# LTEModule.net
KiCad netlist of a schematic drawn in Altium Designer
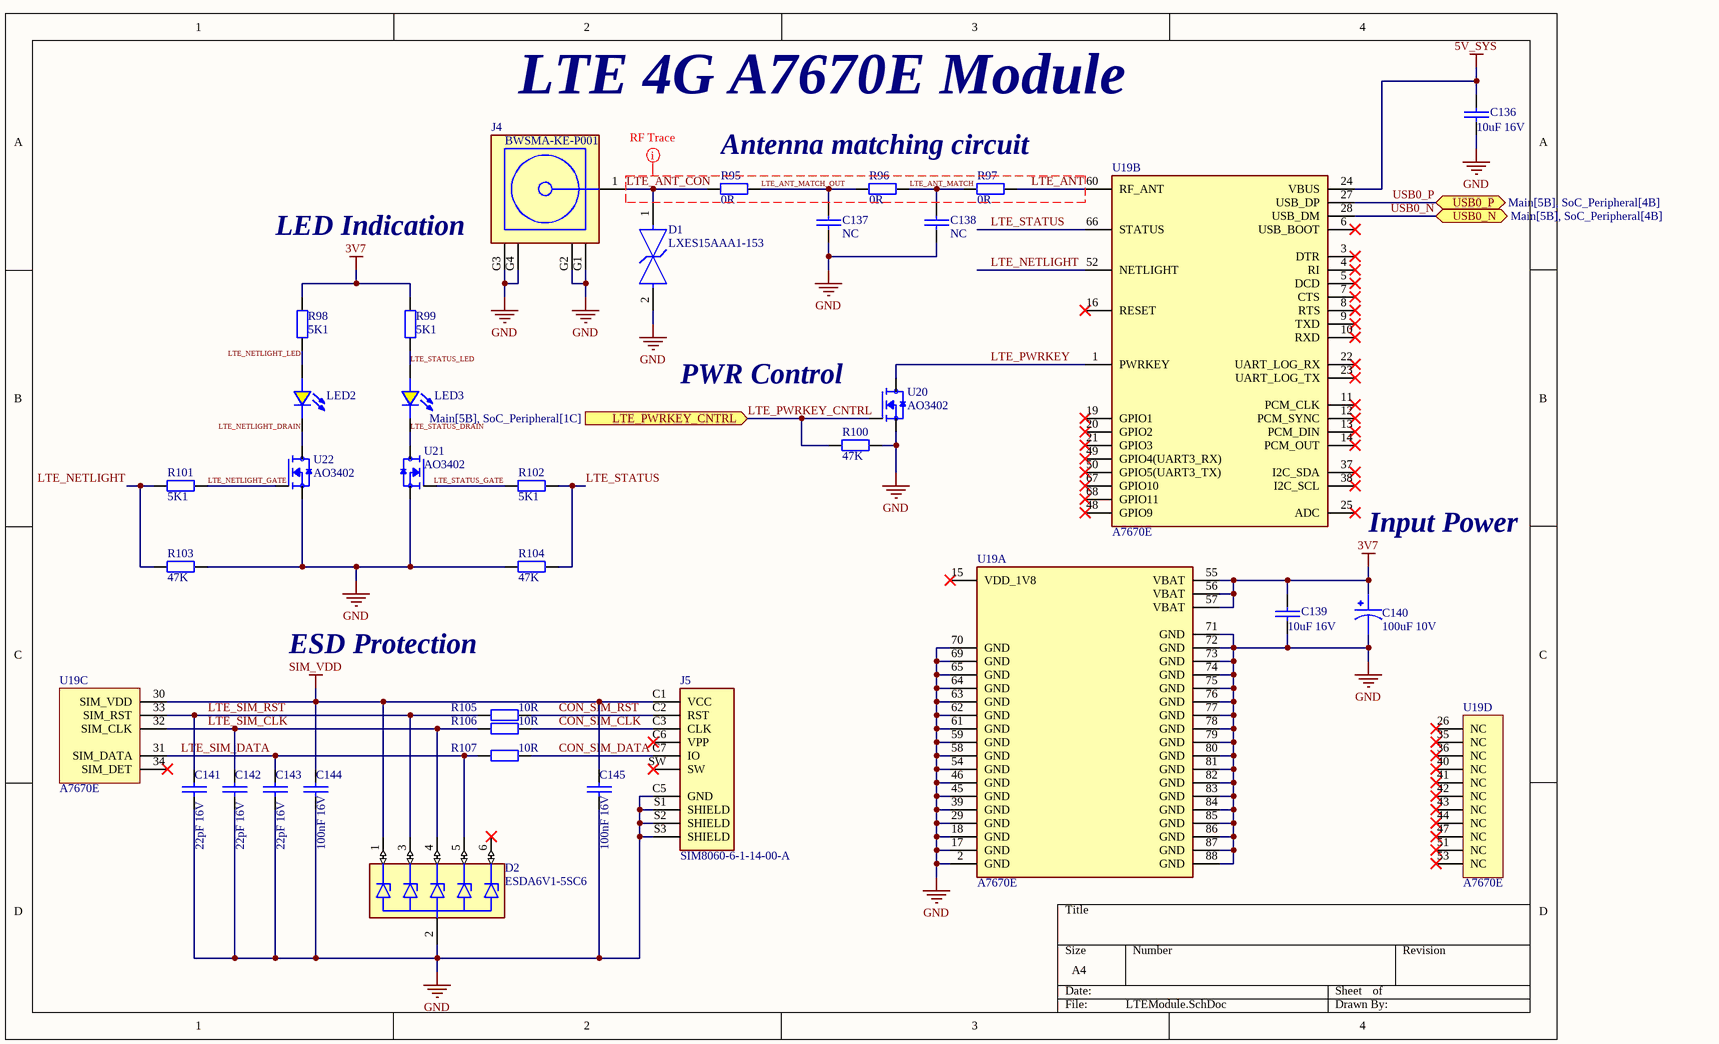
[diagram p0: LTEModule.SchDoc]

(export (version "E")
  (design (tool "Eeschema 10.0.6"))
  (components
    (comp (ref "C136")
      (value "10uF 16V")
      (footprint "C_0603")
      (description "Capacitor 0603 SMD")
      (libsource (lib "tor1kkLib") (part "C_0603"))
    )
    (comp (ref "C137")
      (value "NC")
      (footprint "C_0402")
      (description "Capacitor 0402 SMD")
      (libsource (lib "tor1kkLib") (part "C_0402"))
    )
    (comp (ref "C138")
      (value "NC")
      (footprint "C_0402")
      (description "Capacitor 0402 SMD")
      (libsource (lib "tor1kkLib") (part "C_0402"))
    )
    (comp (ref "C139")
      (value "10uF 16V")
      (footprint "C_0603")
      (description "Capacitor 0603 SMD")
      (libsource (lib "tor1kkLib") (part "C_0603"))
    )
    (comp (ref "C140")
      (value "100uF 10V")
      (footprint "C_CASE-B")
      (description "Tantalum capacitor CASE-B-3528-21")
      (libsource (lib "tor1kkLib") (part "C_CASE-B-3528-21"))
    )
    (comp (ref "C141")
      (value "22pF 16V")
      (footprint "C_0402")
      (description "Capacitor 0402 SMD")
      (libsource (lib "tor1kkLib") (part "C_0402"))
    )
    (comp (ref "C142")
      (value "22pF 16V")
      (footprint "C_0402")
      (description "Capacitor 0402 SMD")
      (libsource (lib "tor1kkLib") (part "C_0402"))
    )
    (comp (ref "C143")
      (value "22pF 16V")
      (footprint "C_0402")
      (description "Capacitor 0402 SMD")
      (libsource (lib "tor1kkLib") (part "C_0402"))
    )
    (comp (ref "C144")
      (value "100nF 16V")
      (footprint "C_0402")
      (description "Capacitor 0402 SMD")
      (libsource (lib "tor1kkLib") (part "C_0402"))
    )
    (comp (ref "C145")
      (value "100nF 16V")
      (footprint "C_0402")
      (description "Capacitor 0402 SMD")
      (libsource (lib "tor1kkLib") (part "C_0402"))
    )
    (comp (ref "D1")
      (value "LXES15AAA1-153")
      (footprint "FP-LXES15-MFG")
      (description "TVS DIODE 4V 1005")
      (libsource (lib "Altium Content Vault") (part "876f4347bf90aa6f500f43e3cd03972"))
    )
    (comp (ref "D2")
      (value "ESDA6V1-5SC6")
      (footprint "SOT-23-6")
      (description "11.4V Clamp 7A (8/20µs) Ipp Tvs Diode Surface Mount SOT-23-6")
      (fields (field (name "MANUFACTURER") "STMicroelectronics"))
      (libsource (lib "tor1kkLib") (part "ESDA6V1-5SC6"))
    )
    (comp (ref "J4")
      (value "BWSMA-KE-P001")
      (footprint "BATWIRELESS_BWSMA-KE-P001")
      (description "1 Inner Hole SMA Board-End Staggered pins 50Ω 5.2mm SMD Coaxial Connectors (RF) ROHS")
      (fields (field (name "MANUFACTURER") "BAT WIRELESS"))
      (libsource (lib "tor1kkLib") (part "BWSMA-KE-P001"))
    )
    (comp (ref "J5")
      (value "SIM8060-6-1-14-00-A")
      (footprint "SIM8060-6-1-14-00-A")
      (description "6 Position Card Connector NANO SIM Surface Mount, Right Angle Gold")
      (fields (field (name "MANUFACTURER") "Global Connector Technology"))
      (libsource (lib "tor1kkLib") (part "SIM8060-6-1-14-00-A"))
    )
    (comp (ref "LED2")
      (value "LED_0603_YELLOW")
      (footprint "LED_0603")
      (libsource (lib "tor1kkLib") (part "LED_0603_YELLOW"))
    )
    (comp (ref "LED3")
      (value "LED_0603_YELLOW")
      (footprint "LED_0603")
      (libsource (lib "tor1kkLib") (part "LED_0603_YELLOW"))
    )
    (comp (ref "R95")
      (value "0R")
      (footprint "R_0402")
      (description "Resistor 0402 SMD")
      (libsource (lib "tor1kkLib") (part "R_0402"))
    )
    (comp (ref "R96")
      (value "0R")
      (footprint "R_0402")
      (description "Resistor 0402 SMD")
      (libsource (lib "tor1kkLib") (part "R_0402"))
    )
    (comp (ref "R97")
      (value "0R")
      (footprint "R_0402")
      (description "Resistor 0402 SMD")
      (libsource (lib "tor1kkLib") (part "R_0402"))
    )
    (comp (ref "R98")
      (value "5K1")
      (footprint "R_0603")
      (description "Resistor 0603 SMD")
      (libsource (lib "tor1kkLib") (part "R_0603"))
    )
    (comp (ref "R99")
      (value "5K1")
      (footprint "R_0603")
      (description "Resistor 0603 SMD")
      (libsource (lib "tor1kkLib") (part "R_0603"))
    )
    (comp (ref "R100")
      (value "47K")
      (footprint "R_0603")
      (description "Resistor 0603 SMD")
      (libsource (lib "") (part "R_0603_1"))
    )
    (comp (ref "R101")
      (value "5K1")
      (footprint "R_0603")
      (description "Resistor 0603 SMD")
      (libsource (lib "") (part "R_0603_1"))
    )
    (comp (ref "R102")
      (value "5K1")
      (footprint "R_0603")
      (description "Resistor 0603 SMD")
      (libsource (lib "") (part "R_0603_1"))
    )
    (comp (ref "R103")
      (value "47K")
      (footprint "R_0603")
      (description "Resistor 0603 SMD")
      (libsource (lib "") (part "R_0603_1"))
    )
    (comp (ref "R104")
      (value "47K")
      (footprint "R_0603")
      (description "Resistor 0603 SMD")
      (libsource (lib "") (part "R_0603_1"))
    )
    (comp (ref "R105")
      (value "10R")
      (footprint "R_0402")
      (description "Resistor 0402 SMD")
      (libsource (lib "") (part "R_0402_1"))
    )
    (comp (ref "R106")
      (value "10R")
      (footprint "R_0402")
      (description "Resistor 0402 SMD")
      (libsource (lib "") (part "R_0402_1"))
    )
    (comp (ref "R107")
      (value "10R")
      (footprint "R_0402")
      (description "Resistor 0402 SMD")
      (libsource (lib "") (part "R_0402_1"))
    )
    (comp (ref "U19")
      (value "A7670E")
      (footprint "A7670")
      (description "LTE Cat 1 module")
      (fields
        (field (name "MANUFACTURER") "SIMCom Wireless Solutions")
        (field (name "MANUFACTURER PART NUMBER") "A7670E-LASE")
      )
      (libsource (lib "tor1kkLib") (part "A7670E"))
    )
    (comp (ref "U20")
      (value "AO3402")
      (footprint "SOT-23-3")
      (description "N-Channel 30 V 4A (Ta) 1.4W (Ta) Surface Mount SOT-23-3")
      (fields (field (name "MANUFACTURER") "Alpha & Omega Semicon"))
      (libsource (lib "tor1kkLib") (part "AO3402"))
    )
    (comp (ref "U21")
      (value "AO3402")
      (footprint "SOT-23-3")
      (description "N-Channel 30 V 4A (Ta) 1.4W (Ta) Surface Mount SOT-23-3")
      (fields (field (name "MANUFACTURER") "Alpha & Omega Semicon"))
      (libsource (lib "tor1kkLib") (part "AO3402"))
    )
    (comp (ref "U22")
      (value "AO3402")
      (footprint "SOT-23-3")
      (description "N-Channel 30 V 4A (Ta) 1.4W (Ta) Surface Mount SOT-23-3")
      (fields (field (name "MANUFACTURER") "Alpha & Omega Semicon"))
      (libsource (lib "tor1kkLib") (part "AO3402"))
    )
  )
  (nets
    (net (code "2") (name "/CON_SIM_CLK") (class "Default")
      (node (ref "J5") (pin "C3") (pinfunction "CLK_C3") (pintype "passive"))
      (node (ref "R106") (pin "1") (pintype "passive"))
    )
    (net (code "3") (name "/CON_SIM_DATA") (class "Default")
      (node (ref "J5") (pin "C7") (pinfunction "IO_C7") (pintype "passive"))
      (node (ref "R107") (pin "1") (pintype "passive"))
    )
    (net (code "4") (name "/CON_SIM_RST") (class "Default")
      (node (ref "J5") (pin "C2") (pinfunction "RST_C2") (pintype "passive"))
      (node (ref "R105") (pin "1") (pintype "passive"))
    )
    (net (code "5") (name "/LTE_ANT") (class "Default")
      (node (ref "R97") (pin "2") (pintype "passive"))
      (node (ref "U19") (pin "60") (pinfunction "RF_ANT_60") (pintype "passive"))
    )
    (net (code "6") (name "/LTE_ANT_CON") (class "Default")
      (node (ref "D1") (pin "1") (pinfunction "1_1") (pintype "passive"))
      (node (ref "J4") (pin "1") (pinfunction "SIG_1") (pintype "passive"))
      (node (ref "R95") (pin "1") (pintype "passive"))
    )
    (net (code "7") (name "/LTE_ANT_MATCH") (class "Default")
      (node (ref "C138") (pin "1") (pintype "passive"))
      (node (ref "R96") (pin "2") (pintype "passive"))
      (node (ref "R97") (pin "1") (pintype "passive"))
    )
    (net (code "8") (name "/LTE_ANT_MATCH_OUT") (class "Default")
      (node (ref "C137") (pin "1") (pintype "passive"))
      (node (ref "R95") (pin "2") (pintype "passive"))
      (node (ref "R96") (pin "1") (pintype "passive"))
    )
    (net (code "9") (name "/LTE_NETLIGHT") (class "Default")
      (node (ref "R101") (pin "1") (pintype "passive"))
      (node (ref "R103") (pin "1") (pintype "passive"))
      (node (ref "U19") (pin "52") (pinfunction "NETLIGHT_52") (pintype "passive"))
    )
    (net (code "10") (name "/LTE_NETLIGHT_DRAIN") (class "Default")
      (node (ref "LED2") (pin "2") (pinfunction "C_2") (pintype "passive"))
      (node (ref "U22") (pin "3") (pinfunction "D_3") (pintype "passive"))
    )
    (net (code "11") (name "/LTE_NETLIGHT_GATE") (class "Default")
      (node (ref "R101") (pin "2") (pintype "passive"))
      (node (ref "U22") (pin "1") (pinfunction "G_1") (pintype "passive"))
    )
    (net (code "12") (name "/LTE_NETLIGHT_LED") (class "Default")
      (node (ref "LED2") (pin "1") (pinfunction "A_1") (pintype "passive"))
      (node (ref "R98") (pin "2") (pintype "passive"))
    )
    (net (code "13") (name "/LTE_PWRKEY") (class "Default")
      (node (ref "U19") (pin "1") (pinfunction "PWRKEY_1") (pintype "passive"))
      (node (ref "U20") (pin "3") (pinfunction "D_3") (pintype "passive"))
    )
    (net (code "14") (name "/LTE_PWRKEY_CNTRL") (class "Default")
      (node (ref "R100") (pin "1") (pintype "passive"))
      (node (ref "U20") (pin "1") (pinfunction "G_1") (pintype "passive"))
    )
    (net (code "15") (name "/LTE_SIM_CLK") (class "Default")
      (node (ref "C142") (pin "1") (pintype "passive"))
      (node (ref "D2") (pin "4") (pinfunction "I/O3_4") (pintype "bidirectional"))
      (node (ref "R106") (pin "2") (pintype "passive"))
      (node (ref "U19") (pin "32") (pinfunction "SIM_CLK_32") (pintype "passive"))
    )
    (net (code "16") (name "/LTE_SIM_DATA") (class "Default")
      (node (ref "C143") (pin "1") (pintype "passive"))
      (node (ref "D2") (pin "5") (pinfunction "I/O4_5") (pintype "bidirectional"))
      (node (ref "R107") (pin "2") (pintype "passive"))
      (node (ref "U19") (pin "31") (pinfunction "SIM_DATA_31") (pintype "passive"))
    )
    (net (code "17") (name "/LTE_SIM_RST") (class "Default")
      (node (ref "C141") (pin "1") (pintype "passive"))
      (node (ref "D2") (pin "3") (pinfunction "I/O2_3") (pintype "bidirectional"))
      (node (ref "R105") (pin "2") (pintype "passive"))
      (node (ref "U19") (pin "33") (pinfunction "SIM_RST_33") (pintype "passive"))
    )
    (net (code "18") (name "/LTE_STATUS") (class "Default")
      (node (ref "R102") (pin "2") (pintype "passive"))
      (node (ref "R104") (pin "2") (pintype "passive"))
      (node (ref "U19") (pin "66") (pinfunction "STATUS_66") (pintype "passive"))
    )
    (net (code "19") (name "/LTE_STATUS_DRAIN") (class "Default")
      (node (ref "LED3") (pin "2") (pinfunction "C_2") (pintype "passive"))
      (node (ref "U21") (pin "3") (pinfunction "D_3") (pintype "passive"))
    )
    (net (code "20") (name "/LTE_STATUS_GATE") (class "Default")
      (node (ref "R102") (pin "1") (pintype "passive"))
      (node (ref "U21") (pin "1") (pinfunction "G_1") (pintype "passive"))
    )
    (net (code "21") (name "/LTE_STATUS_LED") (class "Default")
      (node (ref "LED3") (pin "1") (pinfunction "A_1") (pintype "passive"))
      (node (ref "R99") (pin "2") (pintype "passive"))
    )
    (net (code "22") (name "/USB0_N") (class "Default")
      (node (ref "U19") (pin "28") (pinfunction "USB_DM_28") (pintype "passive"))
    )
    (net (code "23") (name "/USB0_P") (class "Default")
      (node (ref "U19") (pin "27") (pinfunction "USB_DP_27") (pintype "passive"))
    )
    (net (code "24") (name "3V7") (class "Default")
      (node (ref "C139") (pin "1") (pintype "passive"))
      (node (ref "C140") (pin "1") (pinfunction "1_1") (pintype "passive"))
      (node (ref "R98") (pin "1") (pintype "passive"))
      (node (ref "R99") (pin "1") (pintype "passive"))
      (node (ref "U19") (pin "55") (pinfunction "VBAT_55") (pintype "passive"))
      (node (ref "U19") (pin "56") (pinfunction "VBAT_56") (pintype "passive"))
      (node (ref "U19") (pin "57") (pinfunction "VBAT_57") (pintype "passive"))
    )
    (net (code "25") (name "5V_SYS") (class "Default")
      (node (ref "C136") (pin "1") (pintype "passive"))
      (node (ref "U19") (pin "24") (pinfunction "VBUS_24") (pintype "passive"))
    )
    (net (code "26") (name "GND") (class "Default")
      (node (ref "C136") (pin "2") (pintype "passive"))
      (node (ref "C137") (pin "2") (pintype "passive"))
      (node (ref "C138") (pin "2") (pintype "passive"))
      (node (ref "C139") (pin "2") (pintype "passive"))
      (node (ref "C140") (pin "2") (pinfunction "2_2") (pintype "passive"))
      (node (ref "C141") (pin "2") (pintype "passive"))
      (node (ref "C142") (pin "2") (pintype "passive"))
      (node (ref "C143") (pin "2") (pintype "passive"))
      (node (ref "C144") (pin "2") (pintype "passive"))
      (node (ref "C145") (pin "2") (pintype "passive"))
      (node (ref "D1") (pin "2") (pinfunction "2_2") (pintype "passive"))
      (node (ref "D2") (pin "2") (pinfunction "GND_2") (pintype "power_in"))
      (node (ref "J4") (pin "G1") (pinfunction "GND_G1") (pintype "power_in"))
      (node (ref "J4") (pin "G2") (pinfunction "GND_G2") (pintype "power_in"))
      (node (ref "J4") (pin "G3") (pinfunction "GND_G3") (pintype "power_in"))
      (node (ref "J4") (pin "G4") (pinfunction "GND_G4") (pintype "power_in"))
      (node (ref "J5") (pin "C5") (pinfunction "GND_C5") (pintype "passive"))
      (node (ref "J5") (pin "S1") (pinfunction "SHIELD_S1") (pintype "passive"))
      (node (ref "J5") (pin "S2") (pinfunction "SHIELD_S2") (pintype "passive"))
      (node (ref "J5") (pin "S3") (pinfunction "SHIELD_S3") (pintype "passive"))
      (node (ref "R100") (pin "2") (pintype "passive"))
      (node (ref "R103") (pin "2") (pintype "passive"))
      (node (ref "R104") (pin "1") (pintype "passive"))
      (node (ref "U19") (pin "17") (pinfunction "GND_17") (pintype "passive"))
      (node (ref "U19") (pin "18") (pinfunction "GND_18") (pintype "passive"))
      (node (ref "U19") (pin "2") (pinfunction "GND_2") (pintype "passive"))
      (node (ref "U19") (pin "29") (pinfunction "GND_29") (pintype "passive"))
      (node (ref "U19") (pin "39") (pinfunction "GND_39") (pintype "passive"))
      (node (ref "U19") (pin "45") (pinfunction "GND_45") (pintype "passive"))
      (node (ref "U19") (pin "46") (pinfunction "GND_46") (pintype "passive"))
      (node (ref "U19") (pin "54") (pinfunction "GND_54") (pintype "passive"))
      (node (ref "U19") (pin "58") (pinfunction "GND_58") (pintype "passive"))
      (node (ref "U19") (pin "59") (pinfunction "GND_59") (pintype "passive"))
      (node (ref "U19") (pin "61") (pinfunction "GND_61") (pintype "passive"))
      (node (ref "U19") (pin "62") (pinfunction "GND_62") (pintype "passive"))
      (node (ref "U19") (pin "63") (pinfunction "GND_63") (pintype "passive"))
      (node (ref "U19") (pin "64") (pinfunction "GND_64") (pintype "passive"))
      (node (ref "U19") (pin "65") (pinfunction "GND_65") (pintype "passive"))
      (node (ref "U19") (pin "69") (pinfunction "GND_69") (pintype "passive"))
      (node (ref "U19") (pin "70") (pinfunction "GND_70") (pintype "passive"))
      (node (ref "U19") (pin "71") (pinfunction "GND_71") (pintype "passive"))
      (node (ref "U19") (pin "72") (pinfunction "GND_72") (pintype "passive"))
      (node (ref "U19") (pin "73") (pinfunction "GND_73") (pintype "passive"))
      (node (ref "U19") (pin "74") (pinfunction "GND_74") (pintype "passive"))
      (node (ref "U19") (pin "75") (pinfunction "GND_75") (pintype "passive"))
      (node (ref "U19") (pin "76") (pinfunction "GND_76") (pintype "passive"))
      (node (ref "U19") (pin "77") (pinfunction "GND_77") (pintype "passive"))
      (node (ref "U19") (pin "78") (pinfunction "GND_78") (pintype "passive"))
      (node (ref "U19") (pin "79") (pinfunction "GND_79") (pintype "passive"))
      (node (ref "U19") (pin "80") (pinfunction "GND_80") (pintype "passive"))
      (node (ref "U19") (pin "81") (pinfunction "GND_81") (pintype "passive"))
      (node (ref "U19") (pin "82") (pinfunction "GND_82") (pintype "passive"))
      (node (ref "U19") (pin "83") (pinfunction "GND_83") (pintype "passive"))
      (node (ref "U19") (pin "84") (pinfunction "GND_84") (pintype "passive"))
      (node (ref "U19") (pin "85") (pinfunction "GND_85") (pintype "passive"))
      (node (ref "U19") (pin "86") (pinfunction "GND_86") (pintype "passive"))
      (node (ref "U19") (pin "87") (pinfunction "GND_87") (pintype "passive"))
      (node (ref "U19") (pin "88") (pinfunction "GND_88") (pintype "passive"))
      (node (ref "U20") (pin "2") (pinfunction "S_2") (pintype "passive"))
      (node (ref "U21") (pin "2") (pinfunction "S_2") (pintype "passive"))
      (node (ref "U22") (pin "2") (pinfunction "S_2") (pintype "passive"))
    )
    (net (code "27") (name "SIM_VDD") (class "Default")
      (node (ref "C144") (pin "1") (pintype "passive"))
      (node (ref "C145") (pin "1") (pintype "passive"))
      (node (ref "D2") (pin "1") (pinfunction "I/O1_1") (pintype "bidirectional"))
      (node (ref "J5") (pin "C1") (pinfunction "VCC_C1") (pintype "passive"))
      (node (ref "U19") (pin "30") (pinfunction "SIM_VDD_30") (pintype "passive"))
    )
    (net (code "28") (name "unconnected-(D2-I{slash}O5-Pad6)") (class "Default")
      (node (ref "D2") (pin "6") (pinfunction "I/O5_6") (pintype "bidirectional+no_connect"))
    )
    (net (code "29") (name "unconnected-(J5-PadSW)") (class "Default")
      (node (ref "J5") (pin "SW") (pinfunction "SW_SW") (pintype "passive+no_connect"))
    )
    (net (code "30") (name "unconnected-(J5-VPP-PadC6)") (class "Default")
      (node (ref "J5") (pin "C6") (pinfunction "VPP_C6") (pintype "passive+no_connect"))
    )
    (net (code "31") (name "unconnected-(U19A-VDD_1V8-Pad15)") (class "Default")
      (node (ref "U19") (pin "15") (pinfunction "VDD_1V8_15") (pintype "passive+no_connect"))
    )
    (net (code "32") (name "unconnected-(U19B-ADC-Pad25)") (class "Default")
      (node (ref "U19") (pin "25") (pinfunction "ADC_25") (pintype "passive+no_connect"))
    )
    (net (code "33") (name "unconnected-(U19B-CTS-Pad7)") (class "Default")
      (node (ref "U19") (pin "7") (pinfunction "CTS_7") (pintype "passive+no_connect"))
    )
    (net (code "34") (name "unconnected-(U19B-DCD-Pad5)") (class "Default")
      (node (ref "U19") (pin "5") (pinfunction "DCD_5") (pintype "passive+no_connect"))
    )
    (net (code "35") (name "unconnected-(U19B-DTR-Pad3)") (class "Default")
      (node (ref "U19") (pin "3") (pinfunction "DTR_3") (pintype "passive+no_connect"))
    )
    (net (code "36") (name "unconnected-(U19B-GPIO1-Pad19)") (class "Default")
      (node (ref "U19") (pin "19") (pinfunction "GPIO1_19") (pintype "passive+no_connect"))
    )
    (net (code "37") (name "unconnected-(U19B-GPIO2-Pad20)") (class "Default")
      (node (ref "U19") (pin "20") (pinfunction "GPIO2_20") (pintype "passive+no_connect"))
    )
    (net (code "38") (name "unconnected-(U19B-GPIO3-Pad21)") (class "Default")
      (node (ref "U19") (pin "21") (pinfunction "GPIO3_21") (pintype "passive+no_connect"))
    )
    (net (code "39") (name "unconnected-(U19B-GPIO4(UART3_RX)-Pad49)") (class "Default")
      (node (ref "U19") (pin "49") (pinfunction "GPIO4(UART3_RX)_49") (pintype "passive+no_connect"))
    )
    (net (code "40") (name "unconnected-(U19B-GPIO5(UART3_TX)-Pad50)") (class "Default")
      (node (ref "U19") (pin "50") (pinfunction "GPIO5(UART3_TX)_50") (pintype "passive+no_connect"))
    )
    (net (code "41") (name "unconnected-(U19B-GPIO9-Pad48)") (class "Default")
      (node (ref "U19") (pin "48") (pinfunction "GPIO9_48") (pintype "passive+no_connect"))
    )
    (net (code "42") (name "unconnected-(U19B-GPIO10-Pad67)") (class "Default")
      (node (ref "U19") (pin "67") (pinfunction "GPIO10_67") (pintype "passive+no_connect"))
    )
    (net (code "43") (name "unconnected-(U19B-GPIO11-Pad68)") (class "Default")
      (node (ref "U19") (pin "68") (pinfunction "GPIO11_68") (pintype "passive+no_connect"))
    )
    (net (code "44") (name "unconnected-(U19B-I2C_SCL-Pad38)") (class "Default")
      (node (ref "U19") (pin "38") (pinfunction "I2C_SCL_38") (pintype "passive+no_connect"))
    )
    (net (code "45") (name "unconnected-(U19B-I2C_SDA-Pad37)") (class "Default")
      (node (ref "U19") (pin "37") (pinfunction "I2C_SDA_37") (pintype "passive+no_connect"))
    )
    (net (code "46") (name "unconnected-(U19B-PCM_CLK-Pad11)") (class "Default")
      (node (ref "U19") (pin "11") (pinfunction "PCM_CLK_11") (pintype "passive+no_connect"))
    )
    (net (code "47") (name "unconnected-(U19B-PCM_DIN-Pad13)") (class "Default")
      (node (ref "U19") (pin "13") (pinfunction "PCM_DIN_13") (pintype "passive+no_connect"))
    )
    (net (code "48") (name "unconnected-(U19B-PCM_OUT-Pad14)") (class "Default")
      (node (ref "U19") (pin "14") (pinfunction "PCM_OUT_14") (pintype "passive+no_connect"))
    )
    (net (code "49") (name "unconnected-(U19B-PCM_SYNC-Pad12)") (class "Default")
      (node (ref "U19") (pin "12") (pinfunction "PCM_SYNC_12") (pintype "passive+no_connect"))
    )
    (net (code "50") (name "unconnected-(U19B-RESET-Pad16)") (class "Default")
      (node (ref "U19") (pin "16") (pinfunction "RESET_16") (pintype "passive+no_connect"))
    )
    (net (code "51") (name "unconnected-(U19B-RI-Pad4)") (class "Default")
      (node (ref "U19") (pin "4") (pinfunction "RI_4") (pintype "passive+no_connect"))
    )
    (net (code "52") (name "unconnected-(U19B-RTS-Pad8)") (class "Default")
      (node (ref "U19") (pin "8") (pinfunction "RTS_8") (pintype "passive+no_connect"))
    )
    (net (code "53") (name "unconnected-(U19B-RXD-Pad10)") (class "Default")
      (node (ref "U19") (pin "10") (pinfunction "RXD_10") (pintype "passive+no_connect"))
    )
    (net (code "54") (name "unconnected-(U19B-TXD-Pad9)") (class "Default")
      (node (ref "U19") (pin "9") (pinfunction "TXD_9") (pintype "passive+no_connect"))
    )
    (net (code "55") (name "unconnected-(U19B-UART_LOG_RX-Pad22)") (class "Default")
      (node (ref "U19") (pin "22") (pinfunction "UART_LOG_RX_22") (pintype "passive+no_connect"))
    )
    (net (code "56") (name "unconnected-(U19B-UART_LOG_TX-Pad23)") (class "Default")
      (node (ref "U19") (pin "23") (pinfunction "UART_LOG_TX_23") (pintype "passive+no_connect"))
    )
    (net (code "57") (name "unconnected-(U19B-USB_BOOT-Pad6)") (class "Default")
      (node (ref "U19") (pin "6") (pinfunction "USB_BOOT_6") (pintype "passive+no_connect"))
    )
    (net (code "58") (name "unconnected-(U19C-SIM_DET-Pad34)") (class "Default")
      (node (ref "U19") (pin "34") (pinfunction "SIM_DET_34") (pintype "passive+no_connect"))
    )
    (net (code "59") (name "unconnected-(U19D-NC-Pad26)") (class "Default")
      (node (ref "U19") (pin "26") (pinfunction "NC_26") (pintype "passive+no_connect"))
    )
    (net (code "60") (name "unconnected-(U19D-NC-Pad35)") (class "Default")
      (node (ref "U19") (pin "35") (pinfunction "NC_35") (pintype "passive+no_connect"))
    )
    (net (code "61") (name "unconnected-(U19D-NC-Pad36)") (class "Default")
      (node (ref "U19") (pin "36") (pinfunction "NC_36") (pintype "passive+no_connect"))
    )
    (net (code "62") (name "unconnected-(U19D-NC-Pad40)") (class "Default")
      (node (ref "U19") (pin "40") (pinfunction "NC_40") (pintype "passive+no_connect"))
    )
    (net (code "63") (name "unconnected-(U19D-NC-Pad41)") (class "Default")
      (node (ref "U19") (pin "41") (pinfunction "NC_41") (pintype "passive+no_connect"))
    )
    (net (code "64") (name "unconnected-(U19D-NC-Pad42)") (class "Default")
      (node (ref "U19") (pin "42") (pinfunction "NC_42") (pintype "passive+no_connect"))
    )
    (net (code "65") (name "unconnected-(U19D-NC-Pad43)") (class "Default")
      (node (ref "U19") (pin "43") (pinfunction "NC_43") (pintype "passive+no_connect"))
    )
    (net (code "66") (name "unconnected-(U19D-NC-Pad44)") (class "Default")
      (node (ref "U19") (pin "44") (pinfunction "NC_44") (pintype "passive+no_connect"))
    )
    (net (code "67") (name "unconnected-(U19D-NC-Pad47)") (class "Default")
      (node (ref "U19") (pin "47") (pinfunction "NC_47") (pintype "passive+no_connect"))
    )
    (net (code "68") (name "unconnected-(U19D-NC-Pad51)") (class "Default")
      (node (ref "U19") (pin "51") (pinfunction "NC_51") (pintype "passive+no_connect"))
    )
    (net (code "69") (name "unconnected-(U19D-NC-Pad53)") (class "Default")
      (node (ref "U19") (pin "53") (pinfunction "NC_53") (pintype "passive+no_connect"))
    )
  )
)
